# dataBoard.net
KiCad netlist of a schematic drawn in EAGLE
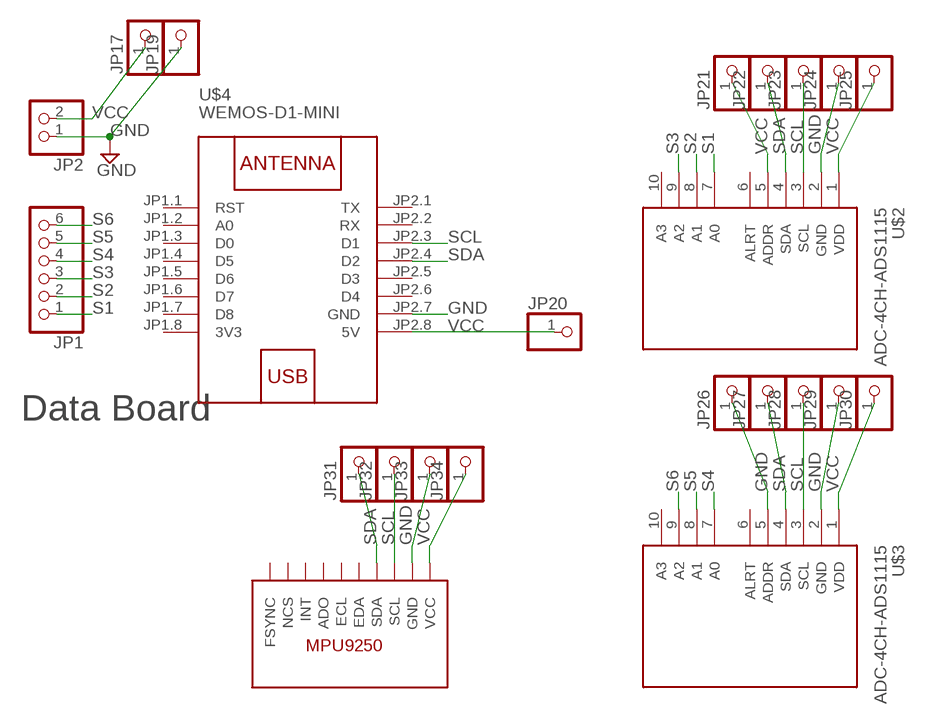
[diagram p0: schematic, sheet 1]

(export (version "E")
  (design (tool "Eeschema 10.0.6"))
  (components
    (comp (ref "JP1")
      (value "PINHD-1X6")
      (footprint "eagle-import:1X06")
      (libsource (lib "eagle-import") (part "PINHD-1X6"))
    )
    (comp (ref "JP2")
      (value "PINHD-1X2")
      (footprint "eagle-import:1X02")
      (libsource (lib "eagle-import") (part "PINHD-1X2"))
    )
    (comp (ref "JP17")
      (value "PINHD-1X1")
      (footprint "eagle-import:1X01")
      (libsource (lib "eagle-import") (part "PINHD-1X1"))
    )
    (comp (ref "JP19")
      (value "PINHD-1X1")
      (footprint "eagle-import:1X01")
      (libsource (lib "eagle-import") (part "PINHD-1X1"))
    )
    (comp (ref "JP20")
      (value "PINHD-1X1")
      (footprint "eagle-import:1X01")
      (libsource (lib "eagle-import") (part "PINHD-1X1"))
    )
    (comp (ref "JP21")
      (value "PINHD-1X1")
      (footprint "eagle-import:1X01")
      (libsource (lib "eagle-import") (part "PINHD-1X1"))
    )
    (comp (ref "JP22")
      (value "PINHD-1X1")
      (footprint "eagle-import:1X01")
      (libsource (lib "eagle-import") (part "PINHD-1X1"))
    )
    (comp (ref "JP23")
      (value "PINHD-1X1")
      (footprint "eagle-import:1X01")
      (libsource (lib "eagle-import") (part "PINHD-1X1"))
    )
    (comp (ref "JP24")
      (value "PINHD-1X1")
      (footprint "eagle-import:1X01")
      (libsource (lib "eagle-import") (part "PINHD-1X1"))
    )
    (comp (ref "JP25")
      (value "PINHD-1X1")
      (footprint "eagle-import:1X01")
      (libsource (lib "eagle-import") (part "PINHD-1X1"))
    )
    (comp (ref "JP26")
      (value "PINHD-1X1")
      (footprint "eagle-import:1X01")
      (libsource (lib "eagle-import") (part "PINHD-1X1"))
    )
    (comp (ref "JP27")
      (value "PINHD-1X1")
      (footprint "eagle-import:1X01")
      (libsource (lib "eagle-import") (part "PINHD-1X1"))
    )
    (comp (ref "JP28")
      (value "PINHD-1X1")
      (footprint "eagle-import:1X01")
      (libsource (lib "eagle-import") (part "PINHD-1X1"))
    )
    (comp (ref "JP29")
      (value "PINHD-1X1")
      (footprint "eagle-import:1X01")
      (libsource (lib "eagle-import") (part "PINHD-1X1"))
    )
    (comp (ref "JP30")
      (value "PINHD-1X1")
      (footprint "eagle-import:1X01")
      (libsource (lib "eagle-import") (part "PINHD-1X1"))
    )
    (comp (ref "JP31")
      (value "PINHD-1X1")
      (footprint "eagle-import:1X01")
      (libsource (lib "eagle-import") (part "PINHD-1X1"))
    )
    (comp (ref "JP32")
      (value "PINHD-1X1")
      (footprint "eagle-import:1X01")
      (libsource (lib "eagle-import") (part "PINHD-1X1"))
    )
    (comp (ref "JP33")
      (value "PINHD-1X1")
      (footprint "eagle-import:1X01")
      (libsource (lib "eagle-import") (part "PINHD-1X1"))
    )
    (comp (ref "JP34")
      (value "PINHD-1X1")
      (footprint "eagle-import:1X01")
      (libsource (lib "eagle-import") (part "PINHD-1X1"))
    )
    (comp (ref "MPU1")
      (value "MPU9250")
      (footprint "eagle-import:MPU9250")
      (libsource (lib "eagle-import") (part "MPU9250"))
    )
    (comp (ref "U$2")
      (value "ADC-4CH-ADS1115")
      (footprint "eagle-import:ADC-4CH-ADS1115")
      (libsource (lib "eagle-import") (part "ADC-4CH-ADS1115"))
    )
    (comp (ref "U$3")
      (value "ADC-4CH-ADS1115")
      (footprint "eagle-import:ADC-4CH-ADS1115")
      (libsource (lib "eagle-import") (part "ADC-4CH-ADS1115"))
    )
    (comp (ref "U$4")
      (value "WEMOS-D1-MINI")
      (footprint "eagle-import:WEMOS-D1-MINI")
      (libsource (lib "eagle-import") (part "WEMOS-D1-MINI"))
    )
  )
  (nets
    (net (code "1") (name "/3V3") (class "Default")
      (node (ref "U$4") (pin "JP1.8") (pinfunction "3V3_JP1.8") (pintype "power_in"))
    )
    (net (code "2") (name "/S1") (class "Default")
      (node (ref "JP1") (pin "1") (pinfunction "1_1") (pintype "passive"))
      (node (ref "U$2") (pin "7") (pinfunction "A0_7") (pintype "input"))
    )
    (net (code "3") (name "/S2") (class "Default")
      (node (ref "JP1") (pin "2") (pinfunction "2_2") (pintype "passive"))
      (node (ref "U$2") (pin "8") (pinfunction "A1_8") (pintype "input"))
    )
    (net (code "4") (name "/S3") (class "Default")
      (node (ref "JP1") (pin "3") (pinfunction "3_3") (pintype "passive"))
      (node (ref "U$2") (pin "9") (pinfunction "A2_9") (pintype "input"))
    )
    (net (code "5") (name "/S4") (class "Default")
      (node (ref "JP1") (pin "4") (pinfunction "4_4") (pintype "passive"))
      (node (ref "U$3") (pin "7") (pinfunction "A0_7") (pintype "input"))
    )
    (net (code "6") (name "/S5") (class "Default")
      (node (ref "JP1") (pin "5") (pinfunction "5_5") (pintype "passive"))
      (node (ref "U$3") (pin "8") (pinfunction "A1_8") (pintype "input"))
    )
    (net (code "7") (name "/S6") (class "Default")
      (node (ref "JP1") (pin "6") (pinfunction "6_6") (pintype "passive"))
      (node (ref "U$3") (pin "9") (pinfunction "A2_9") (pintype "input"))
    )
    (net (code "8") (name "/SCL") (class "Default")
      (node (ref "JP23") (pin "1") (pinfunction "1_1") (pintype "passive"))
      (node (ref "JP28") (pin "1") (pinfunction "1_1") (pintype "passive"))
      (node (ref "JP32") (pin "1") (pinfunction "1_1") (pintype "passive"))
      (node (ref "MPU1") (pin "SCL") (pinfunction "SCL_SCL") (pintype "bidirectional"))
      (node (ref "U$2") (pin "3") (pinfunction "SCL_3") (pintype "bidirectional"))
      (node (ref "U$3") (pin "3") (pinfunction "SCL_3") (pintype "bidirectional"))
      (node (ref "U$4") (pin "JP2.3") (pinfunction "D1_JP2.3") (pintype "bidirectional"))
    )
    (net (code "9") (name "/SDA") (class "Default")
      (node (ref "JP22") (pin "1") (pinfunction "1_1") (pintype "passive"))
      (node (ref "JP27") (pin "1") (pinfunction "1_1") (pintype "passive"))
      (node (ref "JP31") (pin "1") (pinfunction "1_1") (pintype "passive"))
      (node (ref "MPU1") (pin "SDA") (pinfunction "SDA_SDA") (pintype "bidirectional"))
      (node (ref "U$2") (pin "4") (pinfunction "SDA_4") (pintype "bidirectional"))
      (node (ref "U$3") (pin "4") (pinfunction "SDA_4") (pintype "bidirectional"))
      (node (ref "U$4") (pin "JP2.4") (pinfunction "D2_JP2.4") (pintype "bidirectional"))
    )
    (net (code "10") (name "/VCC") (class "Default")
      (node (ref "JP17") (pin "1") (pinfunction "1_1") (pintype "passive"))
      (node (ref "JP2") (pin "2") (pinfunction "2_2") (pintype "passive"))
      (node (ref "JP20") (pin "1") (pinfunction "1_1") (pintype "passive"))
      (node (ref "JP21") (pin "1") (pinfunction "1_1") (pintype "passive"))
      (node (ref "JP25") (pin "1") (pinfunction "1_1") (pintype "passive"))
      (node (ref "JP30") (pin "1") (pinfunction "1_1") (pintype "passive"))
      (node (ref "JP34") (pin "1") (pinfunction "1_1") (pintype "passive"))
      (node (ref "MPU1") (pin "VCC") (pinfunction "VCC_VCC") (pintype "bidirectional"))
      (node (ref "U$2") (pin "1") (pinfunction "VDD_1") (pintype "power_in"))
      (node (ref "U$2") (pin "5") (pinfunction "ADDR_5") (pintype "bidirectional"))
      (node (ref "U$3") (pin "1") (pinfunction "VDD_1") (pintype "power_in"))
      (node (ref "U$4") (pin "JP2.8") (pinfunction "5V_JP2.8") (pintype "power_in"))
    )
    (net (code "11") (name "GND") (class "Default")
      (node (ref "JP19") (pin "1") (pinfunction "1_1") (pintype "passive"))
      (node (ref "JP2") (pin "1") (pinfunction "1_1") (pintype "passive"))
      (node (ref "JP24") (pin "1") (pinfunction "1_1") (pintype "passive"))
      (node (ref "JP26") (pin "1") (pinfunction "1_1") (pintype "passive"))
      (node (ref "JP29") (pin "1") (pinfunction "1_1") (pintype "passive"))
      (node (ref "JP33") (pin "1") (pinfunction "1_1") (pintype "passive"))
      (node (ref "MPU1") (pin "GND") (pinfunction "GND_GND") (pintype "bidirectional"))
      (node (ref "U$2") (pin "2") (pinfunction "GND_2") (pintype "power_in"))
      (node (ref "U$3") (pin "2") (pinfunction "GND_2") (pintype "power_in"))
      (node (ref "U$3") (pin "5") (pinfunction "ADDR_5") (pintype "bidirectional"))
      (node (ref "U$4") (pin "JP2.7") (pinfunction "GND_JP2.7") (pintype "power_in"))
    )
    (net (code "12") (name "unconnected-(MPU1-PadADO)") (class "Default")
      (node (ref "MPU1") (pin "ADO") (pinfunction "ADO_ADO") (pintype "bidirectional"))
    )
    (net (code "13") (name "unconnected-(MPU1-PadECL)") (class "Default")
      (node (ref "MPU1") (pin "ECL") (pinfunction "ECL_ECL") (pintype "bidirectional"))
    )
    (net (code "14") (name "unconnected-(MPU1-PadEDA)") (class "Default")
      (node (ref "MPU1") (pin "EDA") (pinfunction "EDA_EDA") (pintype "bidirectional"))
    )
    (net (code "15") (name "unconnected-(MPU1-PadFSYNC)") (class "Default")
      (node (ref "MPU1") (pin "FSYNC") (pinfunction "FSYNC_FSYNC") (pintype "bidirectional"))
    )
    (net (code "16") (name "unconnected-(MPU1-PadINT)") (class "Default")
      (node (ref "MPU1") (pin "INT") (pinfunction "INT_INT") (pintype "bidirectional"))
    )
    (net (code "17") (name "unconnected-(MPU1-PadNCS)") (class "Default")
      (node (ref "MPU1") (pin "NCS") (pinfunction "NCS_NCS") (pintype "bidirectional"))
    )
    (net (code "18") (name "unconnected-(U$2-A3-Pad10)") (class "Default")
      (node (ref "U$2") (pin "10") (pinfunction "A3_10") (pintype "input"))
    )
    (net (code "19") (name "unconnected-(U$2-ALRT-Pad6)") (class "Default")
      (node (ref "U$2") (pin "6") (pinfunction "ALRT_6") (pintype "bidirectional"))
    )
    (net (code "20") (name "unconnected-(U$3-A3-Pad10)") (class "Default")
      (node (ref "U$3") (pin "10") (pinfunction "A3_10") (pintype "input"))
    )
    (net (code "21") (name "unconnected-(U$3-ALRT-Pad6)") (class "Default")
      (node (ref "U$3") (pin "6") (pinfunction "ALRT_6") (pintype "bidirectional"))
    )
    (net (code "22") (name "unconnected-(U$4-A0-PadJP1.2)") (class "Default")
      (node (ref "U$4") (pin "JP1.2") (pinfunction "A0_JP1.2") (pintype "bidirectional"))
    )
    (net (code "23") (name "unconnected-(U$4-D0-PadJP1.3)") (class "Default")
      (node (ref "U$4") (pin "JP1.3") (pinfunction "D0_JP1.3") (pintype "bidirectional"))
    )
    (net (code "24") (name "unconnected-(U$4-D3-PadJP2.5)") (class "Default")
      (node (ref "U$4") (pin "JP2.5") (pinfunction "D3_JP2.5") (pintype "bidirectional"))
    )
    (net (code "25") (name "unconnected-(U$4-D4-PadJP2.6)") (class "Default")
      (node (ref "U$4") (pin "JP2.6") (pinfunction "D4_JP2.6") (pintype "bidirectional"))
    )
    (net (code "26") (name "unconnected-(U$4-D5-PadJP1.4)") (class "Default")
      (node (ref "U$4") (pin "JP1.4") (pinfunction "D5_JP1.4") (pintype "bidirectional"))
    )
    (net (code "27") (name "unconnected-(U$4-D6-PadJP1.5)") (class "Default")
      (node (ref "U$4") (pin "JP1.5") (pinfunction "D6_JP1.5") (pintype "bidirectional"))
    )
    (net (code "28") (name "unconnected-(U$4-D7-PadJP1.6)") (class "Default")
      (node (ref "U$4") (pin "JP1.6") (pinfunction "D7_JP1.6") (pintype "bidirectional"))
    )
    (net (code "29") (name "unconnected-(U$4-D8-PadJP1.7)") (class "Default")
      (node (ref "U$4") (pin "JP1.7") (pinfunction "D8_JP1.7") (pintype "bidirectional"))
    )
    (net (code "30") (name "unconnected-(U$4-RST-PadJP1.1)") (class "Default")
      (node (ref "U$4") (pin "JP1.1") (pinfunction "RST_JP1.1") (pintype "bidirectional"))
    )
    (net (code "31") (name "unconnected-(U$4-RX-PadJP2.2)") (class "Default")
      (node (ref "U$4") (pin "JP2.2") (pinfunction "RX_JP2.2") (pintype "bidirectional"))
    )
    (net (code "32") (name "unconnected-(U$4-TX-PadJP2.1)") (class "Default")
      (node (ref "U$4") (pin "JP2.1") (pinfunction "TX_JP2.1") (pintype "bidirectional"))
    )
  )
)
